# USB.net
KiCad netlist of a schematic drawn in Altium Designer
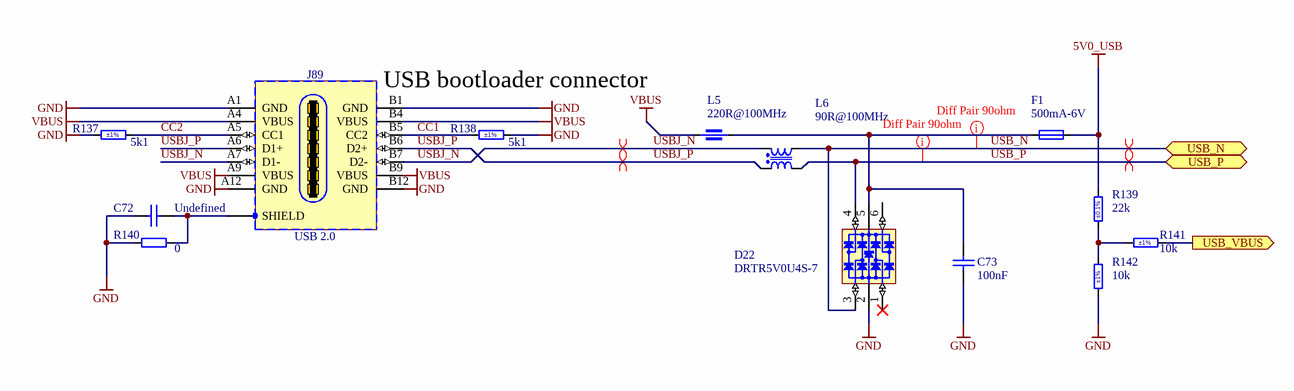
[diagram p0: USB.SchDoc]

(export (version "E")
  (design (tool "Eeschema 10.0.6"))
  (components
    (comp (ref "C72")
      (value "Undefined")
      (footprint "CAPC2012X135N")
      (description "Non-polarised capacitor")
      (fields (field (name "PART NUMBER") "CC0805_NO-VALUE") (field (name "AUTHOR") "CERN DEM JLC"))
      (libsource (lib "Capacitors") (part "Capacitor - non polarized"))
    )
    (comp (ref "C73")
      (value "100nF")
      (footprint "CAPC1608X87N")
      (description "Non-polarised capacitor")
      (fields
        (field (name "PART NUMBER") "CC0603_100NF_50V_10%_X7R")
        (field (name "VOLTAGE") "50V")
        (field (name "AUTHOR") "CERN DEM JLC")
      )
      (libsource (lib "Capacitors") (part "Capacitor - non polarized"))
    )
    (comp (ref "D22")
      (value "DRTR5V0U4S-7")
      (footprint "SOT65P210X110-6N")
      (description "Integrated Quad Ultra-Low Capacitance ESD Protection")
      (fields (field (name "MANUFACTURER") "DIODES") (field (name "AUTHOR") "GK"))
      (libsource (lib "Diodes") (part "D_TVS_DRTR5V0U4S-7"))
    )
    (comp (ref "F1")
      (value "500mA-6V")
      (footprint "FUSR_BOURNS_MF-PSMF050")
      (description "Fuse")
      (fields
        (field (name "PART NUMBER") "FUSR_BOURNS_MF-PSMF050X-2")
        (field (name "MANUFACTURER") "BOURNS")
        (field (name "AUTHOR") "CERN DEM MR")
      )
      (libsource (lib "Eletro-mechanical") (part "Fuse"))
    )
    (comp (ref "J89")
      (value "USB 2.0")
      (footprint "KYCON_KUSBX-SL-CS1N14-B")
      (description "2x7 Pin + 1 Shield  USB Type C Receptacle")
      (fields
        (field (name "PART NUMBER") "KYCON_KUSBX-SL-CS1N14-B")
        (field (name "MANUFACTURER") "KYCON")
        (field (name "AUTHOR") "CERN DEM BC")
      )
      (libsource (lib "Connectors") (part "Connector USB C 14 Pin + 1 Shield"))
    )
    (comp (ref "L5")
      (value "220R@100MHz")
      (footprint "INDC1608X95N")
      (fields
        (field (name "PART NUMBER") "IND0603_MURATA_BLM18SG221TN1")
        (field (name "POWER") "2.5A")
        (field (name "TOLERANCE") "±25%")
        (field (name "AUTHOR") "CERN DEM MR")
      )
      (libsource (lib "Inductors & Transformers") (part "Ferrite Bead"))
    )
    (comp (ref "L6")
      (value "90R@100MHz")
      (footprint "IND_MURATA_DLW21S")
      (description "Inductor Common Mode")
      (fields
        (field (name "PART NUMBER") "IND_MURATA_DLW21SN900SQ2L")
        (field (name "POWER") "330mA")
        (field (name "AUTHOR") "CERN DEM JLC")
      )
      (libsource (lib "Inductors & Transformers") (part "Inductor Common Mode 1Dot-2 4Dot-3"))
    )
    (comp (ref "R137")
      (value "5k1")
      (footprint "RESC1608X55N")
      (description "Resistor - 1%")
      (fields
        (field (name "TOLERANCE") "±1%")
        (field (name "PART NUMBER") "R0603_5K1_1%_0.1W_100PPM")
        (field (name "POWER") "0.1W")
        (field (name "AUTHOR") "CERN DEM JLC")
      )
      (libsource (lib "Resistors") (part "Resistor - 1%"))
    )
    (comp (ref "R138")
      (value "5k1")
      (footprint "RESC1608X55N")
      (description "Resistor - 1%")
      (fields
        (field (name "TOLERANCE") "±1%")
        (field (name "PART NUMBER") "R0603_5K1_1%_0.1W_100PPM")
        (field (name "POWER") "0.1W")
        (field (name "AUTHOR") "CERN DEM JLC")
      )
      (libsource (lib "Resistors") (part "Resistor - 1%"))
    )
    (comp (ref "R139")
      (value "22k")
      (footprint "RESC1608X64N")
      (description "Resistor - 0.1%")
      (fields
        (field (name "TOLERANCE") "±0.1%")
        (field (name "PART NUMBER") "R0603_22K_0.1%_0.1W_25PPM")
        (field (name "POWER") "0.1W")
        (field (name "AUTHOR") "CERN DEM HF")
      )
      (libsource (lib "Resistors") (part "Resistor - 0.1%"))
    )
    (comp (ref "R140")
      (value "0")
      (footprint "RESC1608X55N")
      (description "Resistor")
      (fields
        (field (name "PART NUMBER") "R0603_0R_JUMPER")
        (field (name "MANUFACTURER") "GENERIC")
        (field (name "AUTHOR") "CERN DEM JLC")
      )
      (libsource (lib "Resistors") (part "Resistor"))
    )
    (comp (ref "R141")
      (value "10k")
      (footprint "RESC1608X55N")
      (description "Resistor - 1%")
      (fields
        (field (name "TOLERANCE") "±1%")
        (field (name "PART NUMBER") "R0603_10K_1%_0.1W_100PPM")
        (field (name "POWER") "0.1W")
        (field (name "AUTHOR") "CERN DEM JLC")
      )
      (libsource (lib "Resistors") (part "Resistor - 1%"))
    )
    (comp (ref "R142")
      (value "10k")
      (footprint "RESC1608X55N")
      (description "Resistor - 1%")
      (fields
        (field (name "TOLERANCE") "±1%")
        (field (name "PART NUMBER") "R0603_10K_1%_0.1W_100PPM")
        (field (name "POWER") "0.1W")
        (field (name "AUTHOR") "CERN DEM JLC")
      )
      (libsource (lib "Resistors") (part "Resistor - 1%"))
    )
  )
  (nets
    (net (code "1") (name "/CC1") (class "Default")
      (node (ref "J89") (pin "B5") (pinfunction "CC2_B5") (pintype "bidirectional"))
      (node (ref "R138") (pin "1") (pinfunction "1_1") (pintype "passive"))
    )
    (net (code "2") (name "/CC2") (class "Default")
      (node (ref "J89") (pin "A5") (pinfunction "CC1_A5") (pintype "bidirectional"))
      (node (ref "R137") (pin "2") (pinfunction "2_2") (pintype "passive"))
    )
    (net (code "3") (name "/USBJ_N") (class "Default")
      (node (ref "J89") (pin "A7") (pinfunction "D1-_A7") (pintype "bidirectional"))
      (node (ref "J89") (pin "B7") (pinfunction "D2-_B7") (pintype "bidirectional"))
      (node (ref "L6") (pin "1") (pinfunction "1_1") (pintype "passive"))
    )
    (net (code "4") (name "/USBJ_P") (class "Default")
      (node (ref "J89") (pin "A6") (pinfunction "D1+_A6") (pintype "bidirectional"))
      (node (ref "J89") (pin "B6") (pinfunction "D2+_B6") (pintype "bidirectional"))
      (node (ref "L6") (pin "4") (pinfunction "4_4") (pintype "passive"))
    )
    (net (code "5") (name "/USB_N") (class "Default")
      (node (ref "D22") (pin "3") (pinfunction "I/O2_3") (pintype "bidirectional"))
      (node (ref "L6") (pin "2") (pinfunction "2_2") (pintype "passive"))
    )
    (net (code "6") (name "/USB_P") (class "Default")
      (node (ref "D22") (pin "4") (pinfunction "I/O3_4") (pintype "bidirectional"))
      (node (ref "L6") (pin "3") (pinfunction "3_3") (pintype "passive"))
    )
    (net (code "7") (name "/USB_VBUS") (class "Default")
      (node (ref "R141") (pin "2") (pinfunction "2_2") (pintype "passive"))
    )
    (net (code "8") (name "5V0_USB") (class "Default")
      (node (ref "F1") (pin "1") (pinfunction "1_1") (pintype "passive"))
      (node (ref "R139") (pin "2") (pinfunction "2_2") (pintype "passive"))
    )
    (net (code "9") (name "GND") (class "Default")
      (node (ref "C72") (pin "1") (pinfunction "1_1") (pintype "passive"))
      (node (ref "C73") (pin "1") (pinfunction "1_1") (pintype "passive"))
      (node (ref "D22") (pin "2") (pinfunction "GND_2") (pintype "power_in"))
      (node (ref "J89") (pin "A1") (pinfunction "GND_A1") (pintype "power_in"))
      (node (ref "J89") (pin "A12") (pinfunction "GND_A12") (pintype "power_in"))
      (node (ref "J89") (pin "B1") (pinfunction "GND_B1") (pintype "power_in"))
      (node (ref "J89") (pin "B12") (pinfunction "GND_B12") (pintype "power_in"))
      (node (ref "R137") (pin "1") (pinfunction "1_1") (pintype "passive"))
      (node (ref "R138") (pin "2") (pinfunction "2_2") (pintype "passive"))
      (node (ref "R140") (pin "2") (pinfunction "2_2") (pintype "passive"))
      (node (ref "R142") (pin "1") (pinfunction "1_1") (pintype "passive"))
    )
    (net (code "10") (name "Net-(C72-Pad2)") (class "Default")
      (node (ref "C72") (pin "2") (pinfunction "2_2") (pintype "passive"))
      (node (ref "J89") (pin "SHIELD") (pinfunction "SHIELD_SHIELD") (pintype "power_in"))
      (node (ref "R140") (pin "1") (pinfunction "1_1") (pintype "passive"))
    )
    (net (code "11") (name "Net-(D22-VBUS)") (class "Default")
      (node (ref "C73") (pin "2") (pinfunction "2_2") (pintype "passive"))
      (node (ref "D22") (pin "5") (pinfunction "VBUS_5") (pintype "power_in"))
      (node (ref "F1") (pin "2") (pinfunction "2_2") (pintype "passive"))
      (node (ref "L5") (pin "1") (pinfunction "1_1") (pintype "passive"))
    )
    (net (code "12") (name "Net-(R139-Pad1)") (class "Default")
      (node (ref "R139") (pin "1") (pinfunction "1_1") (pintype "passive"))
      (node (ref "R141") (pin "1") (pinfunction "1_1") (pintype "passive"))
      (node (ref "R142") (pin "2") (pinfunction "2_2") (pintype "passive"))
    )
    (net (code "13") (name "VBUS") (class "Default")
      (node (ref "J89") (pin "A4") (pinfunction "VBUS_A4") (pintype "power_in"))
      (node (ref "J89") (pin "A9") (pinfunction "VBUS_A9") (pintype "power_in"))
      (node (ref "J89") (pin "B4") (pinfunction "VBUS_B4") (pintype "power_in"))
      (node (ref "J89") (pin "B9") (pinfunction "VBUS_B9") (pintype "power_in"))
      (node (ref "L5") (pin "2") (pinfunction "2_2") (pintype "passive"))
    )
    (net (code "14") (name "unconnected-(D22-I{slash}O1-Pad1)") (class "Default")
      (node (ref "D22") (pin "1") (pinfunction "I/O1_1") (pintype "bidirectional+no_connect"))
    )
    (net (code "15") (name "unconnected-(D22-I{slash}O4-Pad6)") (class "Default")
      (node (ref "D22") (pin "6") (pinfunction "I/O4_6") (pintype "bidirectional"))
    )
  )
)
